# HW4.net
KiCad netlist of a schematic drawn in EAGLE
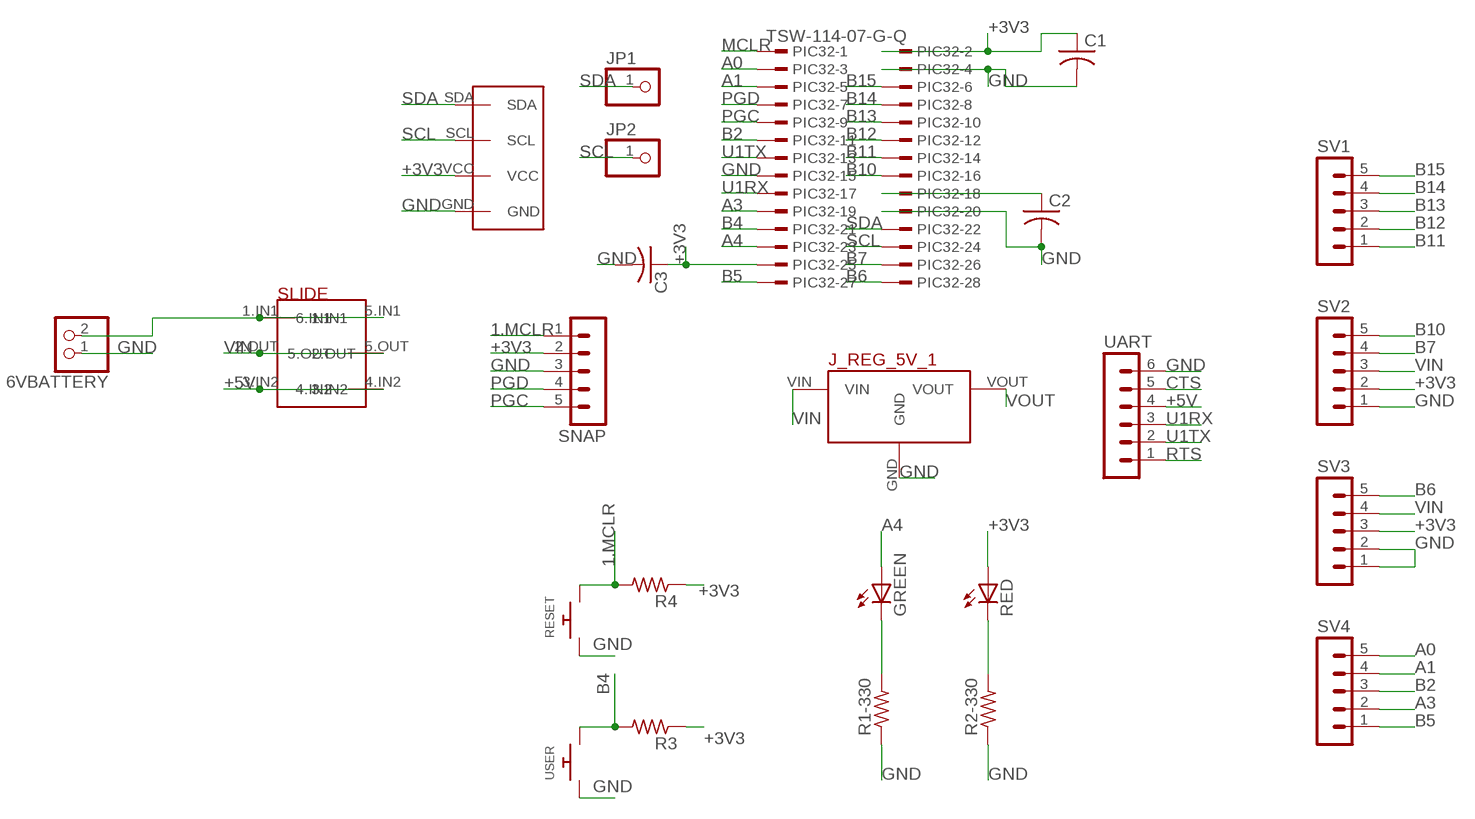
[diagram p0: schematic, sheet 1]

(export (version "E")
  (design (tool "Eeschema 10.0.6"))
  (components
    (comp (ref "6VBATTERY")
      (value "PINHD-1X2")
      (footprint "eagle-import:1X02")
      (libsource (lib "eagle-import") (part "PINHD-1X2"))
    )
    (comp (ref "C1")
      (value "C-US025-025X050")
      (footprint "eagle-import:C025-025X050")
      (libsource (lib "eagle-import") (part "C-US025-025X050"))
    )
    (comp (ref "C2")
      (value "C-US025-025X050")
      (footprint "eagle-import:C025-025X050")
      (libsource (lib "eagle-import") (part "C-US025-025X050"))
    )
    (comp (ref "C3")
      (value "C-US025-025X050")
      (footprint "eagle-import:C025-025X050")
      (libsource (lib "eagle-import") (part "C-US025-025X050"))
    )
    (comp (ref "GREEN")
      (value "LED3MM")
      (footprint "eagle-import:LED3MM")
      (libsource (lib "eagle-import") (part "LED3MM"))
    )
    (comp (ref "JP1")
      (value "PINHD-1X1")
      (footprint "eagle-import:1X01")
      (libsource (lib "eagle-import") (part "PINHD-1X1"))
    )
    (comp (ref "JP2")
      (value "PINHD-1X1")
      (footprint "eagle-import:1X01")
      (libsource (lib "eagle-import") (part "PINHD-1X1"))
    )
    (comp (ref "J_REG_5V_1")
      (value "5V_VOLTAGE_REGULATOR")
      (footprint "eagle-import:5V_VOLTAGE_REGULATOR")
      (libsource (lib "eagle-import") (part "5V_VOLTAGE_REGULATOR"))
    )
    (comp (ref "PIC32")
      (value "TSW-114-07-G-Q")
      (footprint "eagle-import:TSW-114-XX-G-Q")
      (fields (field (name "MF") "Samtec Inc."))
      (libsource (lib "eagle-import") (part "TSW-114--G-Q07"))
    )
    (comp (ref "R1-330")
      (value "R-US_0204/7")
      (footprint "eagle-import:0204_7")
      (libsource (lib "eagle-import") (part "R-US_0204/7"))
    )
    (comp (ref "R2-330")
      (value "R-US_0204/7")
      (footprint "eagle-import:0204_7")
      (libsource (lib "eagle-import") (part "R-US_0204/7"))
    )
    (comp (ref "R3")
      (value "R-US_0204/7")
      (footprint "eagle-import:0204_7")
      (libsource (lib "eagle-import") (part "R-US_0204/7"))
    )
    (comp (ref "R4")
      (value "R-US_0204/7")
      (footprint "eagle-import:0204_7")
      (libsource (lib "eagle-import") (part "R-US_0204/7"))
    )
    (comp (ref "RED")
      (value "LED3MM")
      (footprint "eagle-import:LED3MM")
      (libsource (lib "eagle-import") (part "LED3MM"))
    )
    (comp (ref "RESET")
      (value "SWITCH_PUSHBUTTONSOFTTOUCHSMD_SJ")
      (footprint "eagle-import:PUSHBUTTON_SMD_SJ")
      (libsource (lib "eagle-import") (part "SWITCH_PUSHBUTTONSOFTTOUCHSMD_SJ"))
    )
    (comp (ref "SLIDE")
      (value "SLIDE_DEVICE")
      (footprint "eagle-import:SLIDE_FOOTPRINT")
      (libsource (lib "eagle-import") (part "SLIDE_DEVICE"))
    )
    (comp (ref "SNAP")
      (value "MA05-1")
      (footprint "eagle-import:MA05-1")
      (libsource (lib "eagle-import") (part "MA05-1"))
    )
    (comp (ref "SV1")
      (value "MA05-1")
      (footprint "eagle-import:MA05-1")
      (libsource (lib "eagle-import") (part "MA05-1"))
    )
    (comp (ref "SV2")
      (value "MA05-1")
      (footprint "eagle-import:MA05-1")
      (libsource (lib "eagle-import") (part "MA05-1"))
    )
    (comp (ref "SV3")
      (value "MA05-1")
      (footprint "eagle-import:MA05-1")
      (libsource (lib "eagle-import") (part "MA05-1"))
    )
    (comp (ref "SV4")
      (value "MA05-1")
      (footprint "eagle-import:MA05-1")
      (libsource (lib "eagle-import") (part "MA05-1"))
    )
    (comp (ref "U$1")
      (value "SSD1306_DEVICE")
      (footprint "eagle-import:SSD1306_FOOTPRINT")
      (libsource (lib "eagle-import") (part "SSD1306_DEVICE"))
    )
    (comp (ref "UART")
      (value "MA06-1")
      (footprint "eagle-import:MA06-1")
      (libsource (lib "eagle-import") (part "MA06-1"))
    )
    (comp (ref "USER")
      (value "SWITCH_PUSHBUTTONSOFTTOUCHSMD_SJ")
      (footprint "eagle-import:PUSHBUTTON_SMD_SJ")
      (libsource (lib "eagle-import") (part "SWITCH_PUSHBUTTONSOFTTOUCHSMD_SJ"))
    )
  )
  (nets
    (net (code "1") (name "/+3V3") (class "Default")
      (node (ref "C1") (pin "1") (pinfunction "1_1") (pintype "passive"))
      (node (ref "C3") (pin "1") (pinfunction "1_1") (pintype "passive"))
      (node (ref "PIC32") (pin "2") (pinfunction "1_2") (pintype "passive"))
      (node (ref "PIC32") (pin "25") (pinfunction "1_25") (pintype "passive"))
      (node (ref "R3") (pin "1") (pinfunction "1_1") (pintype "passive"))
      (node (ref "R4") (pin "1") (pinfunction "1_1") (pintype "passive"))
      (node (ref "RED") (pin "A") (pinfunction "A_A") (pintype "passive"))
      (node (ref "SNAP") (pin "2") (pinfunction "2_2") (pintype "passive"))
      (node (ref "SV2") (pin "2") (pinfunction "2_2") (pintype "passive"))
      (node (ref "SV3") (pin "3") (pinfunction "3_3") (pintype "passive"))
      (node (ref "U$1") (pin "VCC") (pinfunction "VCC_VCC") (pintype "bidirectional"))
    )
    (net (code "2") (name "/+5V") (class "Default")
      (node (ref "SLIDE") (pin "3.IN2") (pinfunction "3.IN2_3.IN2") (pintype "bidirectional"))
      (node (ref "SLIDE") (pin "4.IN2") (pinfunction "4.IN2_4.IN2") (pintype "bidirectional"))
      (node (ref "UART") (pin "4") (pinfunction "4_4") (pintype "passive"))
    )
    (net (code "3") (name "/1.MCLR") (class "Default")
      (node (ref "R4") (pin "2") (pinfunction "2_2") (pintype "passive"))
      (node (ref "RESET") (pin "P$2") (pinfunction "P$2_P$2") (pintype "passive"))
      (node (ref "SNAP") (pin "1") (pinfunction "1_1") (pintype "passive"))
    )
    (net (code "4") (name "/A0") (class "Default")
      (node (ref "PIC32") (pin "3") (pinfunction "1_3") (pintype "passive"))
      (node (ref "SV4") (pin "5") (pinfunction "5_5") (pintype "passive"))
    )
    (net (code "5") (name "/A1") (class "Default")
      (node (ref "PIC32") (pin "5") (pinfunction "1_5") (pintype "passive"))
      (node (ref "SV4") (pin "4") (pinfunction "4_4") (pintype "passive"))
    )
    (net (code "6") (name "/A3") (class "Default")
      (node (ref "PIC32") (pin "19") (pinfunction "1_19") (pintype "passive"))
      (node (ref "SV4") (pin "2") (pinfunction "2_2") (pintype "passive"))
    )
    (net (code "7") (name "/A4") (class "Default")
      (node (ref "GREEN") (pin "A") (pinfunction "A_A") (pintype "passive"))
      (node (ref "PIC32") (pin "23") (pinfunction "1_23") (pintype "passive"))
    )
    (net (code "8") (name "/B2") (class "Default")
      (node (ref "PIC32") (pin "11") (pinfunction "1_11") (pintype "passive"))
      (node (ref "SV4") (pin "3") (pinfunction "3_3") (pintype "passive"))
    )
    (net (code "9") (name "/B4") (class "Default")
      (node (ref "PIC32") (pin "21") (pinfunction "1_21") (pintype "passive"))
      (node (ref "R3") (pin "2") (pinfunction "2_2") (pintype "passive"))
      (node (ref "USER") (pin "P$2") (pinfunction "P$2_P$2") (pintype "passive"))
    )
    (net (code "10") (name "/B5") (class "Default")
      (node (ref "PIC32") (pin "27") (pinfunction "1_27") (pintype "passive"))
      (node (ref "SV4") (pin "1") (pinfunction "1_1") (pintype "passive"))
    )
    (net (code "11") (name "/B6") (class "Default")
      (node (ref "PIC32") (pin "28") (pinfunction "1_28") (pintype "passive"))
      (node (ref "SV3") (pin "5") (pinfunction "5_5") (pintype "passive"))
    )
    (net (code "12") (name "/B7") (class "Default")
      (node (ref "PIC32") (pin "26") (pinfunction "1_26") (pintype "passive"))
      (node (ref "SV2") (pin "4") (pinfunction "4_4") (pintype "passive"))
    )
    (net (code "13") (name "/B10") (class "Default")
      (node (ref "PIC32") (pin "16") (pinfunction "1_16") (pintype "passive"))
      (node (ref "SV2") (pin "5") (pinfunction "5_5") (pintype "passive"))
    )
    (net (code "14") (name "/B11") (class "Default")
      (node (ref "PIC32") (pin "14") (pinfunction "1_14") (pintype "passive"))
      (node (ref "SV1") (pin "1") (pinfunction "1_1") (pintype "passive"))
    )
    (net (code "15") (name "/B12") (class "Default")
      (node (ref "PIC32") (pin "12") (pinfunction "1_12") (pintype "passive"))
      (node (ref "SV1") (pin "2") (pinfunction "2_2") (pintype "passive"))
    )
    (net (code "16") (name "/B13") (class "Default")
      (node (ref "PIC32") (pin "10") (pinfunction "1_10") (pintype "passive"))
      (node (ref "SV1") (pin "3") (pinfunction "3_3") (pintype "passive"))
    )
    (net (code "17") (name "/B14") (class "Default")
      (node (ref "PIC32") (pin "8") (pinfunction "1_8") (pintype "passive"))
      (node (ref "SV1") (pin "4") (pinfunction "4_4") (pintype "passive"))
    )
    (net (code "18") (name "/B15") (class "Default")
      (node (ref "PIC32") (pin "6") (pinfunction "1_6") (pintype "passive"))
      (node (ref "SV1") (pin "5") (pinfunction "5_5") (pintype "passive"))
    )
    (net (code "19") (name "/CTS") (class "Default")
      (node (ref "UART") (pin "5") (pinfunction "5_5") (pintype "passive"))
    )
    (net (code "20") (name "/GND") (class "Default")
      (node (ref "6VBATTERY") (pin "1") (pinfunction "1_1") (pintype "passive"))
      (node (ref "C1") (pin "2") (pinfunction "2_2") (pintype "passive"))
      (node (ref "C2") (pin "2") (pinfunction "2_2") (pintype "passive"))
      (node (ref "C3") (pin "2") (pinfunction "2_2") (pintype "passive"))
      (node (ref "J_REG_5V_1") (pin "GND") (pinfunction "GND_GND") (pintype "bidirectional"))
      (node (ref "PIC32") (pin "15") (pinfunction "1_15") (pintype "passive"))
      (node (ref "PIC32") (pin "20") (pinfunction "1_20") (pintype "passive"))
      (node (ref "PIC32") (pin "4") (pinfunction "1_4") (pintype "passive"))
      (node (ref "R1-330") (pin "1") (pinfunction "1_1") (pintype "passive"))
      (node (ref "R2-330") (pin "1") (pinfunction "1_1") (pintype "passive"))
      (node (ref "RESET") (pin "P$1") (pinfunction "P$1_P$1") (pintype "passive"))
      (node (ref "SNAP") (pin "3") (pinfunction "3_3") (pintype "passive"))
      (node (ref "SV2") (pin "1") (pinfunction "1_1") (pintype "passive"))
      (node (ref "SV3") (pin "1") (pinfunction "1_1") (pintype "passive"))
      (node (ref "SV3") (pin "2") (pinfunction "2_2") (pintype "passive"))
      (node (ref "U$1") (pin "GND") (pinfunction "GND_GND") (pintype "bidirectional"))
      (node (ref "UART") (pin "6") (pinfunction "6_6") (pintype "passive"))
      (node (ref "USER") (pin "P$1") (pinfunction "P$1_P$1") (pintype "passive"))
    )
    (net (code "21") (name "/MCLR") (class "Default")
      (node (ref "PIC32") (pin "1") (pinfunction "1_1") (pintype "passive"))
    )
    (net (code "22") (name "/PGC") (class "Default")
      (node (ref "PIC32") (pin "9") (pinfunction "1_9") (pintype "passive"))
      (node (ref "SNAP") (pin "5") (pinfunction "5_5") (pintype "passive"))
    )
    (net (code "23") (name "/PGD") (class "Default")
      (node (ref "PIC32") (pin "7") (pinfunction "1_7") (pintype "passive"))
      (node (ref "SNAP") (pin "4") (pinfunction "4_4") (pintype "passive"))
    )
    (net (code "24") (name "/RTS") (class "Default")
      (node (ref "UART") (pin "1") (pinfunction "1_1") (pintype "passive"))
    )
    (net (code "25") (name "/SCL") (class "Default")
      (node (ref "JP2") (pin "1") (pinfunction "1_1") (pintype "passive"))
      (node (ref "PIC32") (pin "24") (pinfunction "1_24") (pintype "passive"))
      (node (ref "U$1") (pin "SCL") (pinfunction "SCL_SCL") (pintype "bidirectional"))
    )
    (net (code "26") (name "/SDA") (class "Default")
      (node (ref "JP1") (pin "1") (pinfunction "1_1") (pintype "passive"))
      (node (ref "PIC32") (pin "22") (pinfunction "1_22") (pintype "passive"))
      (node (ref "U$1") (pin "SDA") (pinfunction "SDA_SDA") (pintype "bidirectional"))
    )
    (net (code "27") (name "/U1RX") (class "Default")
      (node (ref "PIC32") (pin "17") (pinfunction "1_17") (pintype "passive"))
      (node (ref "UART") (pin "3") (pinfunction "3_3") (pintype "passive"))
    )
    (net (code "28") (name "/U1TX") (class "Default")
      (node (ref "PIC32") (pin "13") (pinfunction "1_13") (pintype "passive"))
      (node (ref "UART") (pin "2") (pinfunction "2_2") (pintype "passive"))
    )
    (net (code "29") (name "/VIN") (class "Default")
      (node (ref "J_REG_5V_1") (pin "VIN") (pinfunction "VIN_VIN") (pintype "bidirectional"))
      (node (ref "SLIDE") (pin "2.OUT") (pinfunction "2.OUT_2.OUT") (pintype "bidirectional"))
      (node (ref "SLIDE") (pin "5.OUT") (pinfunction "5.OUT_5.OUT") (pintype "bidirectional"))
      (node (ref "SV2") (pin "3") (pinfunction "3_3") (pintype "passive"))
      (node (ref "SV3") (pin "4") (pinfunction "4_4") (pintype "passive"))
    )
    (net (code "30") (name "/VOUT") (class "Default")
      (node (ref "J_REG_5V_1") (pin "VOUT") (pinfunction "VOUT_VOUT") (pintype "bidirectional"))
    )
    (net (code "31") (name "Net-(GREEN-C)") (class "Default")
      (node (ref "GREEN") (pin "K") (pinfunction "C_K") (pintype "passive"))
      (node (ref "R1-330") (pin "2") (pinfunction "2_2") (pintype "passive"))
    )
    (net (code "32") (name "Net-(PIC32J-1)") (class "Default")
      (node (ref "C2") (pin "1") (pinfunction "1_1") (pintype "passive"))
      (node (ref "PIC32") (pin "18") (pinfunction "1_18") (pintype "passive"))
    )
    (net (code "33") (name "Net-(RED-C)") (class "Default")
      (node (ref "R2-330") (pin "2") (pinfunction "2_2") (pintype "passive"))
      (node (ref "RED") (pin "K") (pinfunction "C_K") (pintype "passive"))
    )
    (net (code "34") (name "Net-(SLIDE-6.IN1)") (class "Default")
      (node (ref "6VBATTERY") (pin "2") (pinfunction "2_2") (pintype "passive"))
      (node (ref "SLIDE") (pin "1.IN1") (pinfunction "1.IN1_1.IN1") (pintype "bidirectional"))
      (node (ref "SLIDE") (pin "5.IN1") (pinfunction "6.IN1_5.IN1") (pintype "bidirectional"))
    )
  )
)
